# MCU.net
KiCad netlist of a schematic drawn in Altium Designer
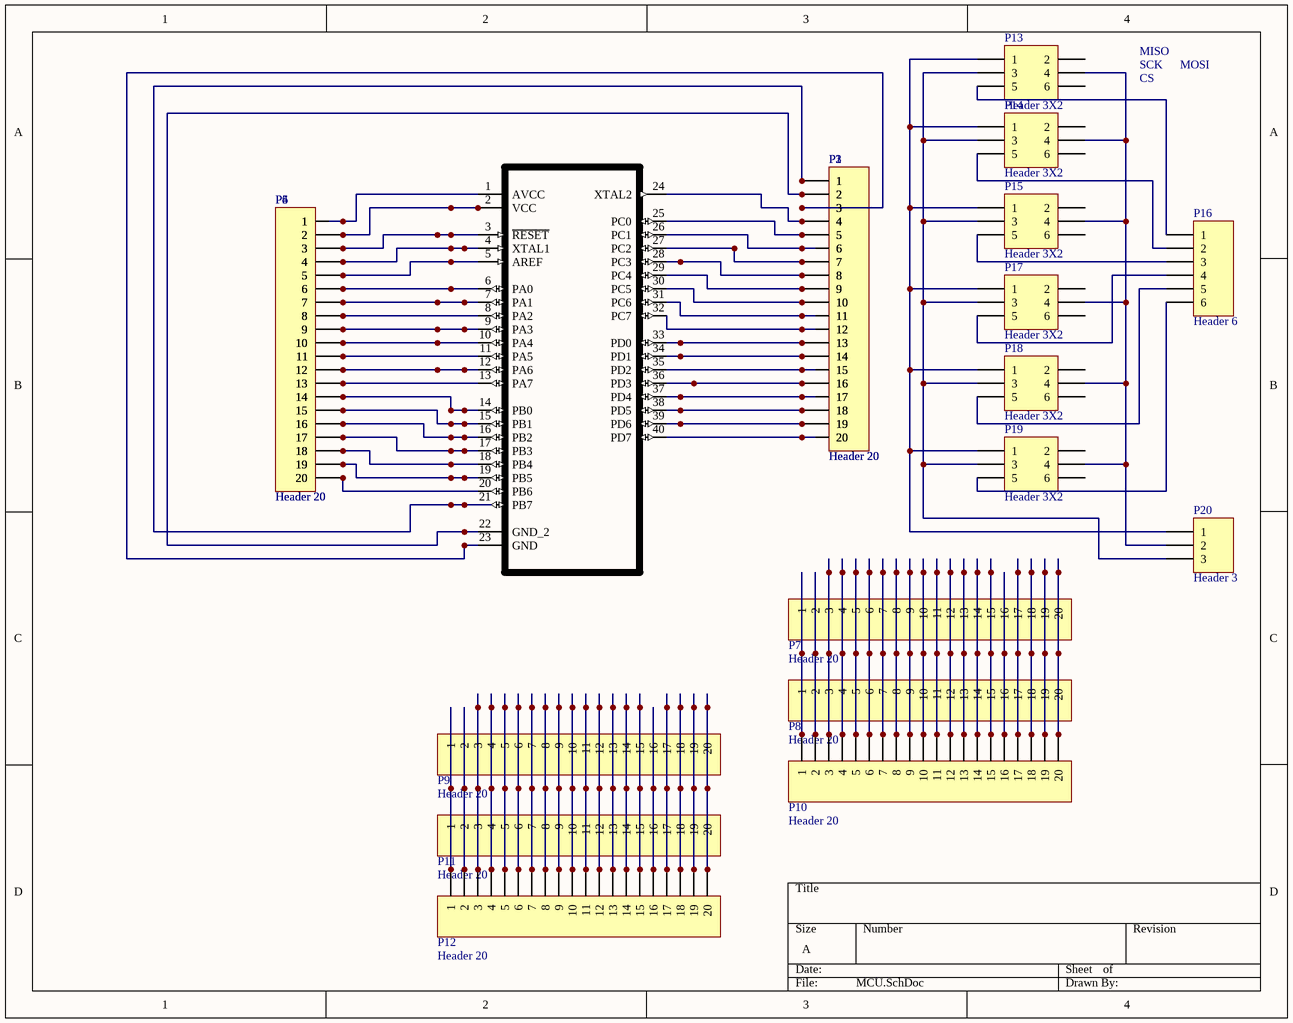
[diagram p0: MCU.SchDoc]

(export (version "E")
  (design (tool "Eeschema 10.0.6"))
  (components
    (comp (ref "P1")
      (value "Header 20")
      (footprint "HDR1X20")
      (description "Header, 20-Pin")
      (fields (field (name "PUBLISHER") "Altium Limited"))
      (libsource (lib "") (part "Header 20_2"))
    )
    (comp (ref "P2")
      (value "Header 20")
      (footprint "HDR1X20")
      (description "Header, 20-Pin")
      (fields (field (name "PUBLISHER") "Altium Limited"))
      (libsource (lib "") (part "Header 20_2"))
    )
    (comp (ref "P3")
      (value "Header 20")
      (footprint "HDR1X20")
      (description "Header, 20-Pin")
      (fields (field (name "PUBLISHER") "Altium Limited"))
      (libsource (lib "") (part "Header 20_2"))
    )
    (comp (ref "P4")
      (value "Header 20")
      (footprint "HDR1X20")
      (description "Header, 20-Pin")
      (fields (field (name "PUBLISHER") "Altium Limited"))
      (libsource (lib "Miscellaneous Connectors") (part "Header 20"))
    )
    (comp (ref "P5")
      (value "Header 20")
      (footprint "HDR1X20")
      (description "Header, 20-Pin")
      (fields (field (name "PUBLISHER") "Altium Limited"))
      (libsource (lib "Miscellaneous Connectors") (part "Header 20"))
    )
    (comp (ref "P6")
      (value "Header 20")
      (footprint "HDR1X20")
      (description "Header, 20-Pin")
      (fields (field (name "PUBLISHER") "Altium Limited"))
      (libsource (lib "Miscellaneous Connectors") (part "Header 20"))
    )
    (comp (ref "P7")
      (value "Header 20")
      (footprint "HDR1X20")
      (description "Header, 20-Pin")
      (fields (field (name "PUBLISHER") "Altium Limited"))
      (libsource (lib "") (part "Header 20_1"))
    )
    (comp (ref "P8")
      (value "Header 20")
      (footprint "HDR1X20")
      (description "Header, 20-Pin")
      (fields (field (name "PUBLISHER") "Altium Limited"))
      (libsource (lib "") (part "Header 20_1"))
    )
    (comp (ref "P9")
      (value "Header 20")
      (footprint "HDR1X20")
      (description "Header, 20-Pin")
      (fields (field (name "PUBLISHER") "Altium Limited"))
      (libsource (lib "") (part "Header 20_1"))
    )
    (comp (ref "P10")
      (value "Header 20")
      (footprint "HDR1X20")
      (description "Header, 20-Pin")
      (fields (field (name "PUBLISHER") "Altium Limited"))
      (libsource (lib "") (part "Header 20_1"))
    )
    (comp (ref "P11")
      (value "Header 20")
      (footprint "HDR1X20")
      (description "Header, 20-Pin")
      (fields (field (name "PUBLISHER") "Altium Limited"))
      (libsource (lib "") (part "Header 20_1"))
    )
    (comp (ref "P12")
      (value "Header 20")
      (footprint "HDR1X20")
      (description "Header, 20-Pin")
      (fields (field (name "PUBLISHER") "Altium Limited"))
      (libsource (lib "") (part "Header 20_1"))
    )
    (comp (ref "P13")
      (value "Header 3X2")
      (footprint "HDR2X3")
      (description "Header, 3-Pin, Dual row")
      (fields (field (name "PUBLISHER") "Altium Limited"))
      (libsource (lib "Miscellaneous Connectors") (part "Header 3X2"))
    )
    (comp (ref "P14")
      (value "Header 3X2")
      (footprint "HDR2X3")
      (description "Header, 3-Pin, Dual row")
      (fields (field (name "PUBLISHER") "Altium Limited"))
      (libsource (lib "Miscellaneous Connectors") (part "Header 3X2"))
    )
    (comp (ref "P15")
      (value "Header 3X2")
      (footprint "HDR2X3")
      (description "Header, 3-Pin, Dual row")
      (fields (field (name "PUBLISHER") "Altium Limited"))
      (libsource (lib "Miscellaneous Connectors") (part "Header 3X2"))
    )
    (comp (ref "P16")
      (value "Header 6")
      (footprint "HDR1X6")
      (description "Header, 6-Pin")
      (fields (field (name "PUBLISHER") "Altium Limited"))
      (libsource (lib "Miscellaneous Connectors") (part "Header 6"))
    )
    (comp (ref "P17")
      (value "Header 3X2")
      (footprint "HDR2X3")
      (description "Header, 3-Pin, Dual row")
      (fields (field (name "PUBLISHER") "Altium Limited"))
      (libsource (lib "Miscellaneous Connectors") (part "Header 3X2"))
    )
    (comp (ref "P18")
      (value "Header 3X2")
      (footprint "HDR2X3")
      (description "Header, 3-Pin, Dual row")
      (fields (field (name "PUBLISHER") "Altium Limited"))
      (libsource (lib "Miscellaneous Connectors") (part "Header 3X2"))
    )
    (comp (ref "P19")
      (value "Header 3X2")
      (footprint "HDR2X3")
      (description "Header, 3-Pin, Dual row")
      (fields (field (name "PUBLISHER") "Altium Limited"))
      (libsource (lib "Miscellaneous Connectors") (part "Header 3X2"))
    )
    (comp (ref "P20")
      (value "Header 3")
      (footprint "HDR1X3")
      (description "Header, 3-Pin")
      (fields (field (name "PUBLISHER") "Altium Limited"))
      (libsource (lib "Miscellaneous Connectors") (part "Header 3"))
    )
    (comp (ref "U1")
      (value "ATMEGA1284P-PU")
      (footprint "DIP254P1524X483-40_ATMEGA1284P-PU(Primary)")
      (libsource (lib "ATMEGA1284P-PU") (part "ATMEGA1284P-PU"))
    )
  )
  (nets
    (net (code "1") (name "Net-(P10-Pad1)") (class "Default")
      (node (ref "P10") (pin "1") (pinfunction "1_1") (pintype "passive"))
      (node (ref "P7") (pin "1") (pinfunction "1_1") (pintype "passive"))
      (node (ref "P8") (pin "1") (pinfunction "1_1") (pintype "passive"))
    )
    (net (code "2") (name "Net-(P10-Pad2)") (class "Default")
      (node (ref "P10") (pin "2") (pinfunction "2_2") (pintype "passive"))
      (node (ref "P7") (pin "2") (pinfunction "2_2") (pintype "passive"))
      (node (ref "P8") (pin "2") (pinfunction "2_2") (pintype "passive"))
    )
    (net (code "3") (name "Net-(P10-Pad3)") (class "Default")
      (node (ref "P10") (pin "3") (pinfunction "3_3") (pintype "passive"))
      (node (ref "P7") (pin "3") (pinfunction "3_3") (pintype "passive"))
      (node (ref "P8") (pin "3") (pinfunction "3_3") (pintype "passive"))
    )
    (net (code "4") (name "Net-(P10-Pad4)") (class "Default")
      (node (ref "P10") (pin "4") (pinfunction "4_4") (pintype "passive"))
      (node (ref "P7") (pin "4") (pinfunction "4_4") (pintype "passive"))
      (node (ref "P8") (pin "4") (pinfunction "4_4") (pintype "passive"))
    )
    (net (code "5") (name "Net-(P10-Pad5)") (class "Default")
      (node (ref "P10") (pin "5") (pinfunction "5_5") (pintype "passive"))
      (node (ref "P7") (pin "5") (pinfunction "5_5") (pintype "passive"))
      (node (ref "P8") (pin "5") (pinfunction "5_5") (pintype "passive"))
    )
    (net (code "6") (name "Net-(P10-Pad6)") (class "Default")
      (node (ref "P10") (pin "6") (pinfunction "6_6") (pintype "passive"))
      (node (ref "P7") (pin "6") (pinfunction "6_6") (pintype "passive"))
      (node (ref "P8") (pin "6") (pinfunction "6_6") (pintype "passive"))
    )
    (net (code "7") (name "Net-(P10-Pad7)") (class "Default")
      (node (ref "P10") (pin "7") (pinfunction "7_7") (pintype "passive"))
      (node (ref "P7") (pin "7") (pinfunction "7_7") (pintype "passive"))
      (node (ref "P8") (pin "7") (pinfunction "7_7") (pintype "passive"))
    )
    (net (code "8") (name "Net-(P10-Pad8)") (class "Default")
      (node (ref "P10") (pin "8") (pinfunction "8_8") (pintype "passive"))
      (node (ref "P7") (pin "8") (pinfunction "8_8") (pintype "passive"))
      (node (ref "P8") (pin "8") (pinfunction "8_8") (pintype "passive"))
    )
    (net (code "9") (name "Net-(P10-Pad9)") (class "Default")
      (node (ref "P10") (pin "9") (pinfunction "9_9") (pintype "passive"))
      (node (ref "P7") (pin "9") (pinfunction "9_9") (pintype "passive"))
      (node (ref "P8") (pin "9") (pinfunction "9_9") (pintype "passive"))
    )
    (net (code "10") (name "Net-(P10-Pad10)") (class "Default")
      (node (ref "P10") (pin "10") (pinfunction "10_10") (pintype "passive"))
      (node (ref "P7") (pin "10") (pinfunction "10_10") (pintype "passive"))
      (node (ref "P8") (pin "10") (pinfunction "10_10") (pintype "passive"))
    )
    (net (code "11") (name "Net-(P10-Pad11)") (class "Default")
      (node (ref "P10") (pin "11") (pinfunction "11_11") (pintype "passive"))
      (node (ref "P7") (pin "11") (pinfunction "11_11") (pintype "passive"))
      (node (ref "P8") (pin "11") (pinfunction "11_11") (pintype "passive"))
    )
    (net (code "12") (name "Net-(P10-Pad12)") (class "Default")
      (node (ref "P10") (pin "12") (pinfunction "12_12") (pintype "passive"))
      (node (ref "P7") (pin "12") (pinfunction "12_12") (pintype "passive"))
      (node (ref "P8") (pin "12") (pinfunction "12_12") (pintype "passive"))
    )
    (net (code "13") (name "Net-(P10-Pad13)") (class "Default")
      (node (ref "P10") (pin "13") (pinfunction "13_13") (pintype "passive"))
      (node (ref "P7") (pin "13") (pinfunction "13_13") (pintype "passive"))
      (node (ref "P8") (pin "13") (pinfunction "13_13") (pintype "passive"))
    )
    (net (code "14") (name "Net-(P10-Pad14)") (class "Default")
      (node (ref "P10") (pin "14") (pinfunction "14_14") (pintype "passive"))
      (node (ref "P7") (pin "14") (pinfunction "14_14") (pintype "passive"))
      (node (ref "P8") (pin "14") (pinfunction "14_14") (pintype "passive"))
    )
    (net (code "15") (name "Net-(P10-Pad15)") (class "Default")
      (node (ref "P10") (pin "15") (pinfunction "15_15") (pintype "passive"))
      (node (ref "P7") (pin "15") (pinfunction "15_15") (pintype "passive"))
      (node (ref "P8") (pin "15") (pinfunction "15_15") (pintype "passive"))
    )
    (net (code "16") (name "Net-(P10-Pad16)") (class "Default")
      (node (ref "P10") (pin "16") (pinfunction "16_16") (pintype "passive"))
      (node (ref "P7") (pin "16") (pinfunction "16_16") (pintype "passive"))
      (node (ref "P8") (pin "16") (pinfunction "16_16") (pintype "passive"))
    )
    (net (code "17") (name "Net-(P10-Pad17)") (class "Default")
      (node (ref "P10") (pin "17") (pinfunction "17_17") (pintype "passive"))
      (node (ref "P7") (pin "17") (pinfunction "17_17") (pintype "passive"))
      (node (ref "P8") (pin "17") (pinfunction "17_17") (pintype "passive"))
    )
    (net (code "18") (name "Net-(P10-Pad18)") (class "Default")
      (node (ref "P10") (pin "18") (pinfunction "18_18") (pintype "passive"))
      (node (ref "P7") (pin "18") (pinfunction "18_18") (pintype "passive"))
      (node (ref "P8") (pin "18") (pinfunction "18_18") (pintype "passive"))
    )
    (net (code "19") (name "Net-(P10-Pad19)") (class "Default")
      (node (ref "P10") (pin "19") (pinfunction "19_19") (pintype "passive"))
      (node (ref "P7") (pin "19") (pinfunction "19_19") (pintype "passive"))
      (node (ref "P8") (pin "19") (pinfunction "19_19") (pintype "passive"))
    )
    (net (code "20") (name "Net-(P10-Pad20)") (class "Default")
      (node (ref "P10") (pin "20") (pinfunction "20_20") (pintype "passive"))
      (node (ref "P7") (pin "20") (pinfunction "20_20") (pintype "passive"))
      (node (ref "P8") (pin "20") (pinfunction "20_20") (pintype "passive"))
    )
    (net (code "21") (name "Net-(P11-Pad1)") (class "Default")
      (node (ref "P11") (pin "1") (pinfunction "1_1") (pintype "passive"))
      (node (ref "P12") (pin "1") (pinfunction "1_1") (pintype "passive"))
      (node (ref "P9") (pin "1") (pinfunction "1_1") (pintype "passive"))
    )
    (net (code "22") (name "Net-(P11-Pad2)") (class "Default")
      (node (ref "P11") (pin "2") (pinfunction "2_2") (pintype "passive"))
      (node (ref "P12") (pin "2") (pinfunction "2_2") (pintype "passive"))
      (node (ref "P9") (pin "2") (pinfunction "2_2") (pintype "passive"))
    )
    (net (code "23") (name "Net-(P11-Pad3)") (class "Default")
      (node (ref "P11") (pin "3") (pinfunction "3_3") (pintype "passive"))
      (node (ref "P12") (pin "3") (pinfunction "3_3") (pintype "passive"))
      (node (ref "P9") (pin "3") (pinfunction "3_3") (pintype "passive"))
    )
    (net (code "24") (name "Net-(P11-Pad4)") (class "Default")
      (node (ref "P11") (pin "4") (pinfunction "4_4") (pintype "passive"))
      (node (ref "P12") (pin "4") (pinfunction "4_4") (pintype "passive"))
      (node (ref "P9") (pin "4") (pinfunction "4_4") (pintype "passive"))
    )
    (net (code "25") (name "Net-(P11-Pad5)") (class "Default")
      (node (ref "P11") (pin "5") (pinfunction "5_5") (pintype "passive"))
      (node (ref "P12") (pin "5") (pinfunction "5_5") (pintype "passive"))
      (node (ref "P9") (pin "5") (pinfunction "5_5") (pintype "passive"))
    )
    (net (code "26") (name "Net-(P11-Pad6)") (class "Default")
      (node (ref "P11") (pin "6") (pinfunction "6_6") (pintype "passive"))
      (node (ref "P12") (pin "6") (pinfunction "6_6") (pintype "passive"))
      (node (ref "P9") (pin "6") (pinfunction "6_6") (pintype "passive"))
    )
    (net (code "27") (name "Net-(P11-Pad7)") (class "Default")
      (node (ref "P11") (pin "7") (pinfunction "7_7") (pintype "passive"))
      (node (ref "P12") (pin "7") (pinfunction "7_7") (pintype "passive"))
      (node (ref "P9") (pin "7") (pinfunction "7_7") (pintype "passive"))
    )
    (net (code "28") (name "Net-(P11-Pad8)") (class "Default")
      (node (ref "P11") (pin "8") (pinfunction "8_8") (pintype "passive"))
      (node (ref "P12") (pin "8") (pinfunction "8_8") (pintype "passive"))
      (node (ref "P9") (pin "8") (pinfunction "8_8") (pintype "passive"))
    )
    (net (code "29") (name "Net-(P11-Pad9)") (class "Default")
      (node (ref "P11") (pin "9") (pinfunction "9_9") (pintype "passive"))
      (node (ref "P12") (pin "9") (pinfunction "9_9") (pintype "passive"))
      (node (ref "P9") (pin "9") (pinfunction "9_9") (pintype "passive"))
    )
    (net (code "30") (name "Net-(P11-Pad10)") (class "Default")
      (node (ref "P11") (pin "10") (pinfunction "10_10") (pintype "passive"))
      (node (ref "P12") (pin "10") (pinfunction "10_10") (pintype "passive"))
      (node (ref "P9") (pin "10") (pinfunction "10_10") (pintype "passive"))
    )
    (net (code "31") (name "Net-(P11-Pad11)") (class "Default")
      (node (ref "P11") (pin "11") (pinfunction "11_11") (pintype "passive"))
      (node (ref "P12") (pin "11") (pinfunction "11_11") (pintype "passive"))
      (node (ref "P9") (pin "11") (pinfunction "11_11") (pintype "passive"))
    )
    (net (code "32") (name "Net-(P11-Pad12)") (class "Default")
      (node (ref "P11") (pin "12") (pinfunction "12_12") (pintype "passive"))
      (node (ref "P12") (pin "12") (pinfunction "12_12") (pintype "passive"))
      (node (ref "P9") (pin "12") (pinfunction "12_12") (pintype "passive"))
    )
    (net (code "33") (name "Net-(P11-Pad13)") (class "Default")
      (node (ref "P11") (pin "13") (pinfunction "13_13") (pintype "passive"))
      (node (ref "P12") (pin "13") (pinfunction "13_13") (pintype "passive"))
      (node (ref "P9") (pin "13") (pinfunction "13_13") (pintype "passive"))
    )
    (net (code "34") (name "Net-(P11-Pad14)") (class "Default")
      (node (ref "P11") (pin "14") (pinfunction "14_14") (pintype "passive"))
      (node (ref "P12") (pin "14") (pinfunction "14_14") (pintype "passive"))
      (node (ref "P9") (pin "14") (pinfunction "14_14") (pintype "passive"))
    )
    (net (code "35") (name "Net-(P11-Pad15)") (class "Default")
      (node (ref "P11") (pin "15") (pinfunction "15_15") (pintype "passive"))
      (node (ref "P12") (pin "15") (pinfunction "15_15") (pintype "passive"))
      (node (ref "P9") (pin "15") (pinfunction "15_15") (pintype "passive"))
    )
    (net (code "36") (name "Net-(P11-Pad16)") (class "Default")
      (node (ref "P11") (pin "16") (pinfunction "16_16") (pintype "passive"))
      (node (ref "P12") (pin "16") (pinfunction "16_16") (pintype "passive"))
      (node (ref "P9") (pin "16") (pinfunction "16_16") (pintype "passive"))
    )
    (net (code "37") (name "Net-(P11-Pad17)") (class "Default")
      (node (ref "P11") (pin "17") (pinfunction "17_17") (pintype "passive"))
      (node (ref "P12") (pin "17") (pinfunction "17_17") (pintype "passive"))
      (node (ref "P9") (pin "17") (pinfunction "17_17") (pintype "passive"))
    )
    (net (code "38") (name "Net-(P11-Pad18)") (class "Default")
      (node (ref "P11") (pin "18") (pinfunction "18_18") (pintype "passive"))
      (node (ref "P12") (pin "18") (pinfunction "18_18") (pintype "passive"))
      (node (ref "P9") (pin "18") (pinfunction "18_18") (pintype "passive"))
    )
    (net (code "39") (name "Net-(P11-Pad19)") (class "Default")
      (node (ref "P11") (pin "19") (pinfunction "19_19") (pintype "passive"))
      (node (ref "P12") (pin "19") (pinfunction "19_19") (pintype "passive"))
      (node (ref "P9") (pin "19") (pinfunction "19_19") (pintype "passive"))
    )
    (net (code "40") (name "Net-(P11-Pad20)") (class "Default")
      (node (ref "P11") (pin "20") (pinfunction "20_20") (pintype "passive"))
      (node (ref "P12") (pin "20") (pinfunction "20_20") (pintype "passive"))
      (node (ref "P9") (pin "20") (pinfunction "20_20") (pintype "passive"))
    )
    (net (code "41") (name "Net-(P13-Pad1)") (class "Default")
      (node (ref "P13") (pin "1") (pinfunction "1_1") (pintype "passive"))
      (node (ref "P14") (pin "1") (pinfunction "1_1") (pintype "passive"))
      (node (ref "P15") (pin "1") (pinfunction "1_1") (pintype "passive"))
      (node (ref "P17") (pin "1") (pinfunction "1_1") (pintype "passive"))
      (node (ref "P18") (pin "1") (pinfunction "1_1") (pintype "passive"))
      (node (ref "P19") (pin "1") (pinfunction "1_1") (pintype "passive"))
      (node (ref "P20") (pin "1") (pinfunction "1_1") (pintype "passive"))
    )
    (net (code "42") (name "Net-(P13-Pad3)") (class "Default")
      (node (ref "P13") (pin "3") (pinfunction "3_3") (pintype "passive"))
      (node (ref "P14") (pin "3") (pinfunction "3_3") (pintype "passive"))
      (node (ref "P15") (pin "3") (pinfunction "3_3") (pintype "passive"))
      (node (ref "P17") (pin "3") (pinfunction "3_3") (pintype "passive"))
      (node (ref "P18") (pin "3") (pinfunction "3_3") (pintype "passive"))
      (node (ref "P19") (pin "3") (pinfunction "3_3") (pintype "passive"))
      (node (ref "P20") (pin "3") (pinfunction "3_3") (pintype "passive"))
    )
    (net (code "43") (name "Net-(P13-Pad4)") (class "Default")
      (node (ref "P13") (pin "4") (pinfunction "4_4") (pintype "passive"))
      (node (ref "P14") (pin "4") (pinfunction "4_4") (pintype "passive"))
      (node (ref "P15") (pin "4") (pinfunction "4_4") (pintype "passive"))
      (node (ref "P17") (pin "4") (pinfunction "4_4") (pintype "passive"))
      (node (ref "P18") (pin "4") (pinfunction "4_4") (pintype "passive"))
      (node (ref "P19") (pin "4") (pinfunction "4_4") (pintype "passive"))
      (node (ref "P20") (pin "2") (pinfunction "2_2") (pintype "passive"))
    )
    (net (code "44") (name "Net-(P13-Pad5)") (class "Default")
      (node (ref "P13") (pin "5") (pinfunction "5_5") (pintype "passive"))
      (node (ref "P16") (pin "1") (pinfunction "1_1") (pintype "passive"))
    )
    (net (code "45") (name "Net-(P14-Pad5)") (class "Default")
      (node (ref "P14") (pin "5") (pinfunction "5_5") (pintype "passive"))
      (node (ref "P16") (pin "2") (pinfunction "2_2") (pintype "passive"))
    )
    (net (code "46") (name "Net-(P15-Pad5)") (class "Default")
      (node (ref "P15") (pin "5") (pinfunction "5_5") (pintype "passive"))
      (node (ref "P16") (pin "3") (pinfunction "3_3") (pintype "passive"))
    )
    (net (code "47") (name "Net-(P16-Pad4)") (class "Default")
      (node (ref "P16") (pin "4") (pinfunction "4_4") (pintype "passive"))
      (node (ref "P17") (pin "5") (pinfunction "5_5") (pintype "passive"))
    )
    (net (code "48") (name "Net-(P16-Pad5)") (class "Default")
      (node (ref "P16") (pin "5") (pinfunction "5_5") (pintype "passive"))
      (node (ref "P18") (pin "5") (pinfunction "5_5") (pintype "passive"))
    )
    (net (code "49") (name "Net-(P16-Pad6)") (class "Default")
      (node (ref "P16") (pin "6") (pinfunction "6_6") (pintype "passive"))
      (node (ref "P19") (pin "5") (pinfunction "5_5") (pintype "passive"))
    )
    (net (code "50") (name "Net-(U1-AREF)") (class "Default")
      (node (ref "P4") (pin "5") (pinfunction "5_5") (pintype "passive"))
      (node (ref "P5") (pin "5") (pinfunction "5_5") (pintype "passive"))
      (node (ref "P6") (pin "5") (pinfunction "5_5") (pintype "passive"))
      (node (ref "U1") (pin "5") (pinfunction "AREF_5") (pintype "input"))
    )
    (net (code "51") (name "Net-(U1-AVCC)") (class "Default")
      (node (ref "P4") (pin "1") (pinfunction "1_1") (pintype "passive"))
      (node (ref "P5") (pin "1") (pinfunction "1_1") (pintype "passive"))
      (node (ref "P6") (pin "1") (pinfunction "1_1") (pintype "passive"))
      (node (ref "U1") (pin "1") (pinfunction "AVCC_1") (pintype "power_in"))
    )
    (net (code "52") (name "Net-(U1-GND)") (class "Default")
      (node (ref "P1") (pin "3") (pinfunction "3_3") (pintype "passive"))
      (node (ref "P2") (pin "3") (pinfunction "3_3") (pintype "passive"))
      (node (ref "P3") (pin "3") (pinfunction "3_3") (pintype "passive"))
      (node (ref "U1") (pin "23") (pinfunction "GND_23") (pintype "passive"))
    )
    (net (code "53") (name "Net-(U1-GND_2)") (class "Default")
      (node (ref "P1") (pin "2") (pinfunction "2_2") (pintype "passive"))
      (node (ref "P2") (pin "2") (pinfunction "2_2") (pintype "passive"))
      (node (ref "P3") (pin "2") (pinfunction "2_2") (pintype "passive"))
      (node (ref "U1") (pin "22") (pinfunction "GND_2_22") (pintype "passive"))
    )
    (net (code "54") (name "Net-(U1-PA0)") (class "Default")
      (node (ref "P4") (pin "6") (pinfunction "6_6") (pintype "passive"))
      (node (ref "P5") (pin "6") (pinfunction "6_6") (pintype "passive"))
      (node (ref "P6") (pin "6") (pinfunction "6_6") (pintype "passive"))
      (node (ref "U1") (pin "6") (pinfunction "PA0_6") (pintype "bidirectional"))
    )
    (net (code "55") (name "Net-(U1-PA1)") (class "Default")
      (node (ref "P4") (pin "7") (pinfunction "7_7") (pintype "passive"))
      (node (ref "P5") (pin "7") (pinfunction "7_7") (pintype "passive"))
      (node (ref "P6") (pin "7") (pinfunction "7_7") (pintype "passive"))
      (node (ref "U1") (pin "7") (pinfunction "PA1_7") (pintype "bidirectional"))
    )
    (net (code "56") (name "Net-(U1-PA2)") (class "Default")
      (node (ref "P4") (pin "8") (pinfunction "8_8") (pintype "passive"))
      (node (ref "P5") (pin "8") (pinfunction "8_8") (pintype "passive"))
      (node (ref "P6") (pin "8") (pinfunction "8_8") (pintype "passive"))
      (node (ref "U1") (pin "8") (pinfunction "PA2_8") (pintype "bidirectional"))
    )
    (net (code "57") (name "Net-(U1-PA3)") (class "Default")
      (node (ref "P4") (pin "9") (pinfunction "9_9") (pintype "passive"))
      (node (ref "P5") (pin "9") (pinfunction "9_9") (pintype "passive"))
      (node (ref "P6") (pin "9") (pinfunction "9_9") (pintype "passive"))
      (node (ref "U1") (pin "9") (pinfunction "PA3_9") (pintype "bidirectional"))
    )
    (net (code "58") (name "Net-(U1-PA4)") (class "Default")
      (node (ref "P4") (pin "10") (pinfunction "10_10") (pintype "passive"))
      (node (ref "P5") (pin "10") (pinfunction "10_10") (pintype "passive"))
      (node (ref "P6") (pin "10") (pinfunction "10_10") (pintype "passive"))
      (node (ref "U1") (pin "10") (pinfunction "PA4_10") (pintype "bidirectional"))
    )
    (net (code "59") (name "Net-(U1-PA5)") (class "Default")
      (node (ref "P4") (pin "11") (pinfunction "11_11") (pintype "passive"))
      (node (ref "P5") (pin "11") (pinfunction "11_11") (pintype "passive"))
      (node (ref "P6") (pin "11") (pinfunction "11_11") (pintype "passive"))
      (node (ref "U1") (pin "11") (pinfunction "PA5_11") (pintype "bidirectional"))
    )
    (net (code "60") (name "Net-(U1-PA6)") (class "Default")
      (node (ref "P4") (pin "12") (pinfunction "12_12") (pintype "passive"))
      (node (ref "P5") (pin "12") (pinfunction "12_12") (pintype "passive"))
      (node (ref "P6") (pin "12") (pinfunction "12_12") (pintype "passive"))
      (node (ref "U1") (pin "12") (pinfunction "PA6_12") (pintype "bidirectional"))
    )
    (net (code "61") (name "Net-(U1-PA7)") (class "Default")
      (node (ref "P4") (pin "13") (pinfunction "13_13") (pintype "passive"))
      (node (ref "P5") (pin "13") (pinfunction "13_13") (pintype "passive"))
      (node (ref "P6") (pin "13") (pinfunction "13_13") (pintype "passive"))
      (node (ref "U1") (pin "13") (pinfunction "PA7_13") (pintype "bidirectional"))
    )
    (net (code "62") (name "Net-(U1-PB0)") (class "Default")
      (node (ref "P4") (pin "14") (pinfunction "14_14") (pintype "passive"))
      (node (ref "P5") (pin "14") (pinfunction "14_14") (pintype "passive"))
      (node (ref "P6") (pin "14") (pinfunction "14_14") (pintype "passive"))
      (node (ref "U1") (pin "14") (pinfunction "PB0_14") (pintype "bidirectional"))
    )
    (net (code "63") (name "Net-(U1-PB1)") (class "Default")
      (node (ref "P4") (pin "15") (pinfunction "15_15") (pintype "passive"))
      (node (ref "P5") (pin "15") (pinfunction "15_15") (pintype "passive"))
      (node (ref "P6") (pin "15") (pinfunction "15_15") (pintype "passive"))
      (node (ref "U1") (pin "15") (pinfunction "PB1_15") (pintype "bidirectional"))
    )
    (net (code "64") (name "Net-(U1-PB2)") (class "Default")
      (node (ref "P4") (pin "16") (pinfunction "16_16") (pintype "passive"))
      (node (ref "P5") (pin "16") (pinfunction "16_16") (pintype "passive"))
      (node (ref "P6") (pin "16") (pinfunction "16_16") (pintype "passive"))
      (node (ref "U1") (pin "16") (pinfunction "PB2_16") (pintype "bidirectional"))
    )
    (net (code "65") (name "Net-(U1-PB3)") (class "Default")
      (node (ref "P4") (pin "17") (pinfunction "17_17") (pintype "passive"))
      (node (ref "P5") (pin "17") (pinfunction "17_17") (pintype "passive"))
      (node (ref "P6") (pin "17") (pinfunction "17_17") (pintype "passive"))
      (node (ref "U1") (pin "17") (pinfunction "PB3_17") (pintype "bidirectional"))
    )
    (net (code "66") (name "Net-(U1-PB4)") (class "Default")
      (node (ref "P4") (pin "18") (pinfunction "18_18") (pintype "passive"))
      (node (ref "P5") (pin "18") (pinfunction "18_18") (pintype "passive"))
      (node (ref "P6") (pin "18") (pinfunction "18_18") (pintype "passive"))
      (node (ref "U1") (pin "18") (pinfunction "PB4_18") (pintype "bidirectional"))
    )
    (net (code "67") (name "Net-(U1-PB5)") (class "Default")
      (node (ref "P4") (pin "19") (pinfunction "19_19") (pintype "passive"))
      (node (ref "P5") (pin "19") (pinfunction "19_19") (pintype "passive"))
      (node (ref "P6") (pin "19") (pinfunction "19_19") (pintype "passive"))
      (node (ref "U1") (pin "19") (pinfunction "PB5_19") (pintype "bidirectional"))
    )
    (net (code "68") (name "Net-(U1-PB6)") (class "Default")
      (node (ref "P4") (pin "20") (pinfunction "20_20") (pintype "passive"))
      (node (ref "P5") (pin "20") (pinfunction "20_20") (pintype "passive"))
      (node (ref "P6") (pin "20") (pinfunction "20_20") (pintype "passive"))
      (node (ref "U1") (pin "20") (pinfunction "PB6_20") (pintype "bidirectional"))
    )
    (net (code "69") (name "Net-(U1-PB7)") (class "Default")
      (node (ref "P1") (pin "1") (pinfunction "1_1") (pintype "passive"))
      (node (ref "P2") (pin "1") (pinfunction "1_1") (pintype "passive"))
      (node (ref "P3") (pin "1") (pinfunction "1_1") (pintype "passive"))
      (node (ref "U1") (pin "21") (pinfunction "PB7_21") (pintype "bidirectional"))
    )
    (net (code "70") (name "Net-(U1-PC0)") (class "Default")
      (node (ref "P1") (pin "5") (pinfunction "5_5") (pintype "passive"))
      (node (ref "P2") (pin "5") (pinfunction "5_5") (pintype "passive"))
      (node (ref "P3") (pin "5") (pinfunction "5_5") (pintype "passive"))
      (node (ref "U1") (pin "25") (pinfunction "PC0_25") (pintype "bidirectional"))
    )
    (net (code "71") (name "Net-(U1-PC1)") (class "Default")
      (node (ref "P1") (pin "6") (pinfunction "6_6") (pintype "passive"))
      (node (ref "P2") (pin "6") (pinfunction "6_6") (pintype "passive"))
      (node (ref "P3") (pin "6") (pinfunction "6_6") (pintype "passive"))
      (node (ref "U1") (pin "26") (pinfunction "PC1_26") (pintype "bidirectional"))
    )
    (net (code "72") (name "Net-(U1-PC2)") (class "Default")
      (node (ref "P1") (pin "7") (pinfunction "7_7") (pintype "passive"))
      (node (ref "P2") (pin "7") (pinfunction "7_7") (pintype "passive"))
      (node (ref "P3") (pin "7") (pinfunction "7_7") (pintype "passive"))
      (node (ref "U1") (pin "27") (pinfunction "PC2_27") (pintype "bidirectional"))
    )
    (net (code "73") (name "Net-(U1-PC3)") (class "Default")
      (node (ref "P1") (pin "8") (pinfunction "8_8") (pintype "passive"))
      (node (ref "P2") (pin "8") (pinfunction "8_8") (pintype "passive"))
      (node (ref "P3") (pin "8") (pinfunction "8_8") (pintype "passive"))
      (node (ref "U1") (pin "28") (pinfunction "PC3_28") (pintype "bidirectional"))
    )
    (net (code "74") (name "Net-(U1-PC4)") (class "Default")
      (node (ref "P1") (pin "9") (pinfunction "9_9") (pintype "passive"))
      (node (ref "P2") (pin "9") (pinfunction "9_9") (pintype "passive"))
      (node (ref "P3") (pin "9") (pinfunction "9_9") (pintype "passive"))
      (node (ref "U1") (pin "29") (pinfunction "PC4_29") (pintype "bidirectional"))
    )
    (net (code "75") (name "Net-(U1-PC5)") (class "Default")
      (node (ref "P1") (pin "10") (pinfunction "10_10") (pintype "passive"))
      (node (ref "P2") (pin "10") (pinfunction "10_10") (pintype "passive"))
      (node (ref "P3") (pin "10") (pinfunction "10_10") (pintype "passive"))
      (node (ref "U1") (pin "30") (pinfunction "PC5_30") (pintype "bidirectional"))
    )
    (net (code "76") (name "Net-(U1-PC6)") (class "Default")
      (node (ref "P1") (pin "11") (pinfunction "11_11") (pintype "passive"))
      (node (ref "P2") (pin "11") (pinfunction "11_11") (pintype "passive"))
      (node (ref "P3") (pin "11") (pinfunction "11_11") (pintype "passive"))
      (node (ref "U1") (pin "31") (pinfunction "PC6_31") (pintype "bidirectional"))
    )
    (net (code "77") (name "Net-(U1-PC7)") (class "Default")
      (node (ref "P1") (pin "12") (pinfunction "12_12") (pintype "passive"))
      (node (ref "P2") (pin "12") (pinfunction "12_12") (pintype "passive"))
      (node (ref "P3") (pin "12") (pinfunction "12_12") (pintype "passive"))
      (node (ref "U1") (pin "32") (pinfunction "PC7_32") (pintype "bidirectional"))
    )
    (net (code "78") (name "Net-(U1-PD0)") (class "Default")
      (node (ref "P1") (pin "13") (pinfunction "13_13") (pintype "passive"))
      (node (ref "P2") (pin "13") (pinfunction "13_13") (pintype "passive"))
      (node (ref "P3") (pin "13") (pinfunction "13_13") (pintype "passive"))
      (node (ref "U1") (pin "33") (pinfunction "PD0_33") (pintype "bidirectional"))
    )
    (net (code "79") (name "Net-(U1-PD1)") (class "Default")
      (node (ref "P1") (pin "14") (pinfunction "14_14") (pintype "passive"))
      (node (ref "P2") (pin "14") (pinfunction "14_14") (pintype "passive"))
      (node (ref "P3") (pin "14") (pinfunction "14_14") (pintype "passive"))
      (node (ref "U1") (pin "34") (pinfunction "PD1_34") (pintype "bidirectional"))
    )
    (net (code "80") (name "Net-(U1-PD2)") (class "Default")
      (node (ref "P1") (pin "15") (pinfunction "15_15") (pintype "passive"))
      (node (ref "P2") (pin "15") (pinfunction "15_15") (pintype "passive"))
      (node (ref "P3") (pin "15") (pinfunction "15_15") (pintype "passive"))
      (node (ref "U1") (pin "35") (pinfunction "PD2_35") (pintype "bidirectional"))
    )
    (net (code "81") (name "Net-(U1-PD3)") (class "Default")
      (node (ref "P1") (pin "16") (pinfunction "16_16") (pintype "passive"))
      (node (ref "P2") (pin "16") (pinfunction "16_16") (pintype "passive"))
      (node (ref "P3") (pin "16") (pinfunction "16_16") (pintype "passive"))
      (node (ref "U1") (pin "36") (pinfunction "PD3_36") (pintype "bidirectional"))
    )
    (net (code "82") (name "Net-(U1-PD4)") (class "Default")
      (node (ref "P1") (pin "17") (pinfunction "17_17") (pintype "passive"))
      (node (ref "P2") (pin "17") (pinfunction "17_17") (pintype "passive"))
      (node (ref "P3") (pin "17") (pinfunction "17_17") (pintype "passive"))
      (node (ref "U1") (pin "37") (pinfunction "PD4_37") (pintype "bidirectional"))
    )
    (net (code "83") (name "Net-(U1-PD5)") (class "Default")
      (node (ref "P1") (pin "18") (pinfunction "18_18") (pintype "passive"))
      (node (ref "P2") (pin "18") (pinfunction "18_18") (pintype "passive"))
      (node (ref "P3") (pin "18") (pinfunction "18_18") (pintype "passive"))
      (node (ref "U1") (pin "38") (pinfunction "PD5_38") (pintype "bidirectional"))
    )
    (net (code "84") (name "Net-(U1-PD6)") (class "Default")
      (node (ref "P1") (pin "19") (pinfunction "19_19") (pintype "passive"))
      (node (ref "P2") (pin "19") (pinfunction "19_19") (pintype "passive"))
      (node (ref "P3") (pin "19") (pinfunction "19_19") (pintype "passive"))
      (node (ref "U1") (pin "39") (pinfunction "PD6_39") (pintype "bidirectional"))
    )
    (net (code "85") (name "Net-(U1-PD7)") (class "Default")
      (node (ref "P1") (pin "20") (pinfunction "20_20") (pintype "passive"))
      (node (ref "P2") (pin "20") (pinfunction "20_20") (pintype "passive"))
      (node (ref "P3") (pin "20") (pinfunction "20_20") (pintype "passive"))
      (node (ref "U1") (pin "40") (pinfunction "PD7_40") (pintype "bidirectional"))
    )
    (net (code "86") (name "Net-(U1-VCC)") (class "Default")
      (node (ref "P4") (pin "2") (pinfunction "2_2") (pintype "passive"))
      (node (ref "P5") (pin "2") (pinfunction "2_2") (pintype "passive"))
      (node (ref "P6") (pin "2") (pinfunction "2_2") (pintype "passive"))
      (node (ref "U1") (pin "2") (pinfunction "VCC_2") (pintype "power_in"))
    )
    (net (code "87") (name "Net-(U1-XTAL1)") (class "Default")
      (node (ref "P4") (pin "4") (pinfunction "4_4") (pintype "passive"))
      (node (ref "P5") (pin "4") (pinfunction "4_4") (pintype "passive"))
      (node (ref "P6") (pin "4") (pinfunction "4_4") (pintype "passive"))
      (node (ref "U1") (pin "4") (pinfunction "XTAL1_4") (pintype "input"))
    )
    (net (code "88") (name "Net-(U1-XTAL2)") (class "Default")
      (node (ref "P1") (pin "4") (pinfunction "4_4") (pintype "passive"))
      (node (ref "P2") (pin "4") (pinfunction "4_4") (pintype "passive"))
      (node (ref "P3") (pin "4") (pinfunction "4_4") (pintype "passive"))
      (node (ref "U1") (pin "24") (pinfunction "XTAL2_24") (pintype "output"))
    )
    (net (code "89") (name "Net-(U1-~{RESET})") (class "Default")
      (node (ref "P4") (pin "3") (pinfunction "3_3") (pintype "passive"))
      (node (ref "P5") (pin "3") (pinfunction "3_3") (pintype "passive"))
      (node (ref "P6") (pin "3") (pinfunction "3_3") (pintype "passive"))
      (node (ref "U1") (pin "3") (pinfunction "~{RESET}_3") (pintype "input"))
    )
    (net (code "90") (name "unconnected-(P13-Pad2)") (class "Default")
      (node (ref "P13") (pin "2") (pinfunction "2_2") (pintype "passive"))
    )
    (net (code "91") (name "unconnected-(P13-Pad6)") (class "Default")
      (node (ref "P13") (pin "6") (pinfunction "6_6") (pintype "passive"))
    )
    (net (code "92") (name "unconnected-(P14-Pad2)") (class "Default")
      (node (ref "P14") (pin "2") (pinfunction "2_2") (pintype "passive"))
    )
    (net (code "93") (name "unconnected-(P14-Pad6)") (class "Default")
      (node (ref "P14") (pin "6") (pinfunction "6_6") (pintype "passive"))
    )
    (net (code "94") (name "unconnected-(P15-Pad2)") (class "Default")
      (node (ref "P15") (pin "2") (pinfunction "2_2") (pintype "passive"))
    )
    (net (code "95") (name "unconnected-(P15-Pad6)") (class "Default")
      (node (ref "P15") (pin "6") (pinfunction "6_6") (pintype "passive"))
    )
    (net (code "96") (name "unconnected-(P17-Pad2)") (class "Default")
      (node (ref "P17") (pin "2") (pinfunction "2_2") (pintype "passive"))
    )
    (net (code "97") (name "unconnected-(P17-Pad6)") (class "Default")
      (node (ref "P17") (pin "6") (pinfunction "6_6") (pintype "passive"))
    )
    (net (code "98") (name "unconnected-(P18-Pad2)") (class "Default")
      (node (ref "P18") (pin "2") (pinfunction "2_2") (pintype "passive"))
    )
    (net (code "99") (name "unconnected-(P18-Pad6)") (class "Default")
      (node (ref "P18") (pin "6") (pinfunction "6_6") (pintype "passive"))
    )
    (net (code "100") (name "unconnected-(P19-Pad2)") (class "Default")
      (node (ref "P19") (pin "2") (pinfunction "2_2") (pintype "passive"))
    )
    (net (code "101") (name "unconnected-(P19-Pad6)") (class "Default")
      (node (ref "P19") (pin "6") (pinfunction "6_6") (pintype "passive"))
    )
  )
)
